# STEMMA.net
KiCad netlist of a schematic drawn in Altium Designer
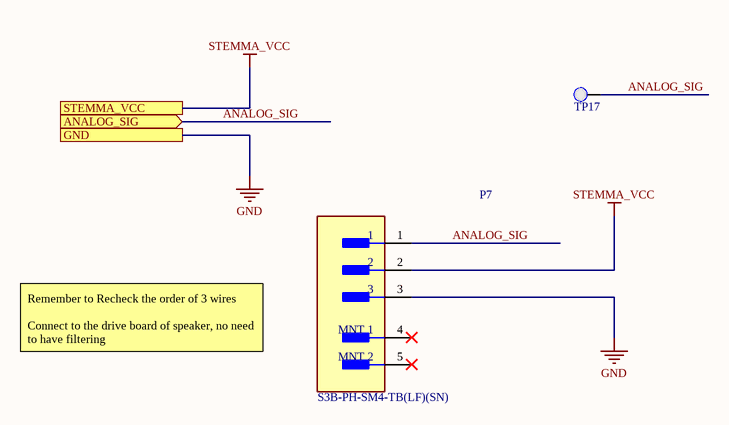
[diagram p0: STEMMA.SchDoc]

(export (version "E")
  (design (tool "Eeschema 10.0.6"))
  (components
    (comp (ref "P7")
      (value "S3B-PH-SM4-TB(LF)(SN)")
      (footprint "FP-S3B-PH-SM4-TB_LF_SN-MFG")
      (description "CONN HEADER SMD R/A 3POS 2MM")
      (libsource (lib "Altium Content Vault") (part "38689d6f3df0f9b234c6ddcef280d85"))
    )
    (comp (ref "TP17")
      (value "Test Point 0.1\"")
      (footprint "Test Point 0.1\"-Footprint-1")
      (libsource (lib "University of Pennsylvania (ESE Labs)") (part "Test Point 0.1{dblquote}-Symbol-1"))
    )
  )
  (nets
    (net (code "1") (name "/ANALOG_SIG") (class "Default")
      (node (ref "P7") (pin "1") (pinfunction "1_1") (pintype "passive"))
      (node (ref "TP17") (pin "1") (pinfunction "PAD_1") (pintype "passive"))
    )
    (net (code "2") (name "GND") (class "Default")
      (node (ref "P7") (pin "3") (pinfunction "3_3") (pintype "passive"))
    )
    (net (code "3") (name "STEMMA_VCC") (class "Default")
      (node (ref "P7") (pin "2") (pinfunction "2_2") (pintype "passive"))
    )
    (net (code "4") (name "unconnected-(P7-MNT_1-Pad4)") (class "Default")
      (node (ref "P7") (pin "4") (pinfunction "MNT_1_4") (pintype "passive+no_connect"))
    )
    (net (code "5") (name "unconnected-(P7-MNT_2-Pad5)") (class "Default")
      (node (ref "P7") (pin "5") (pinfunction "MNT_2_5") (pintype "passive+no_connect"))
    )
  )
)
